# clock.net
KiCad netlist of a schematic drawn in EAGLE
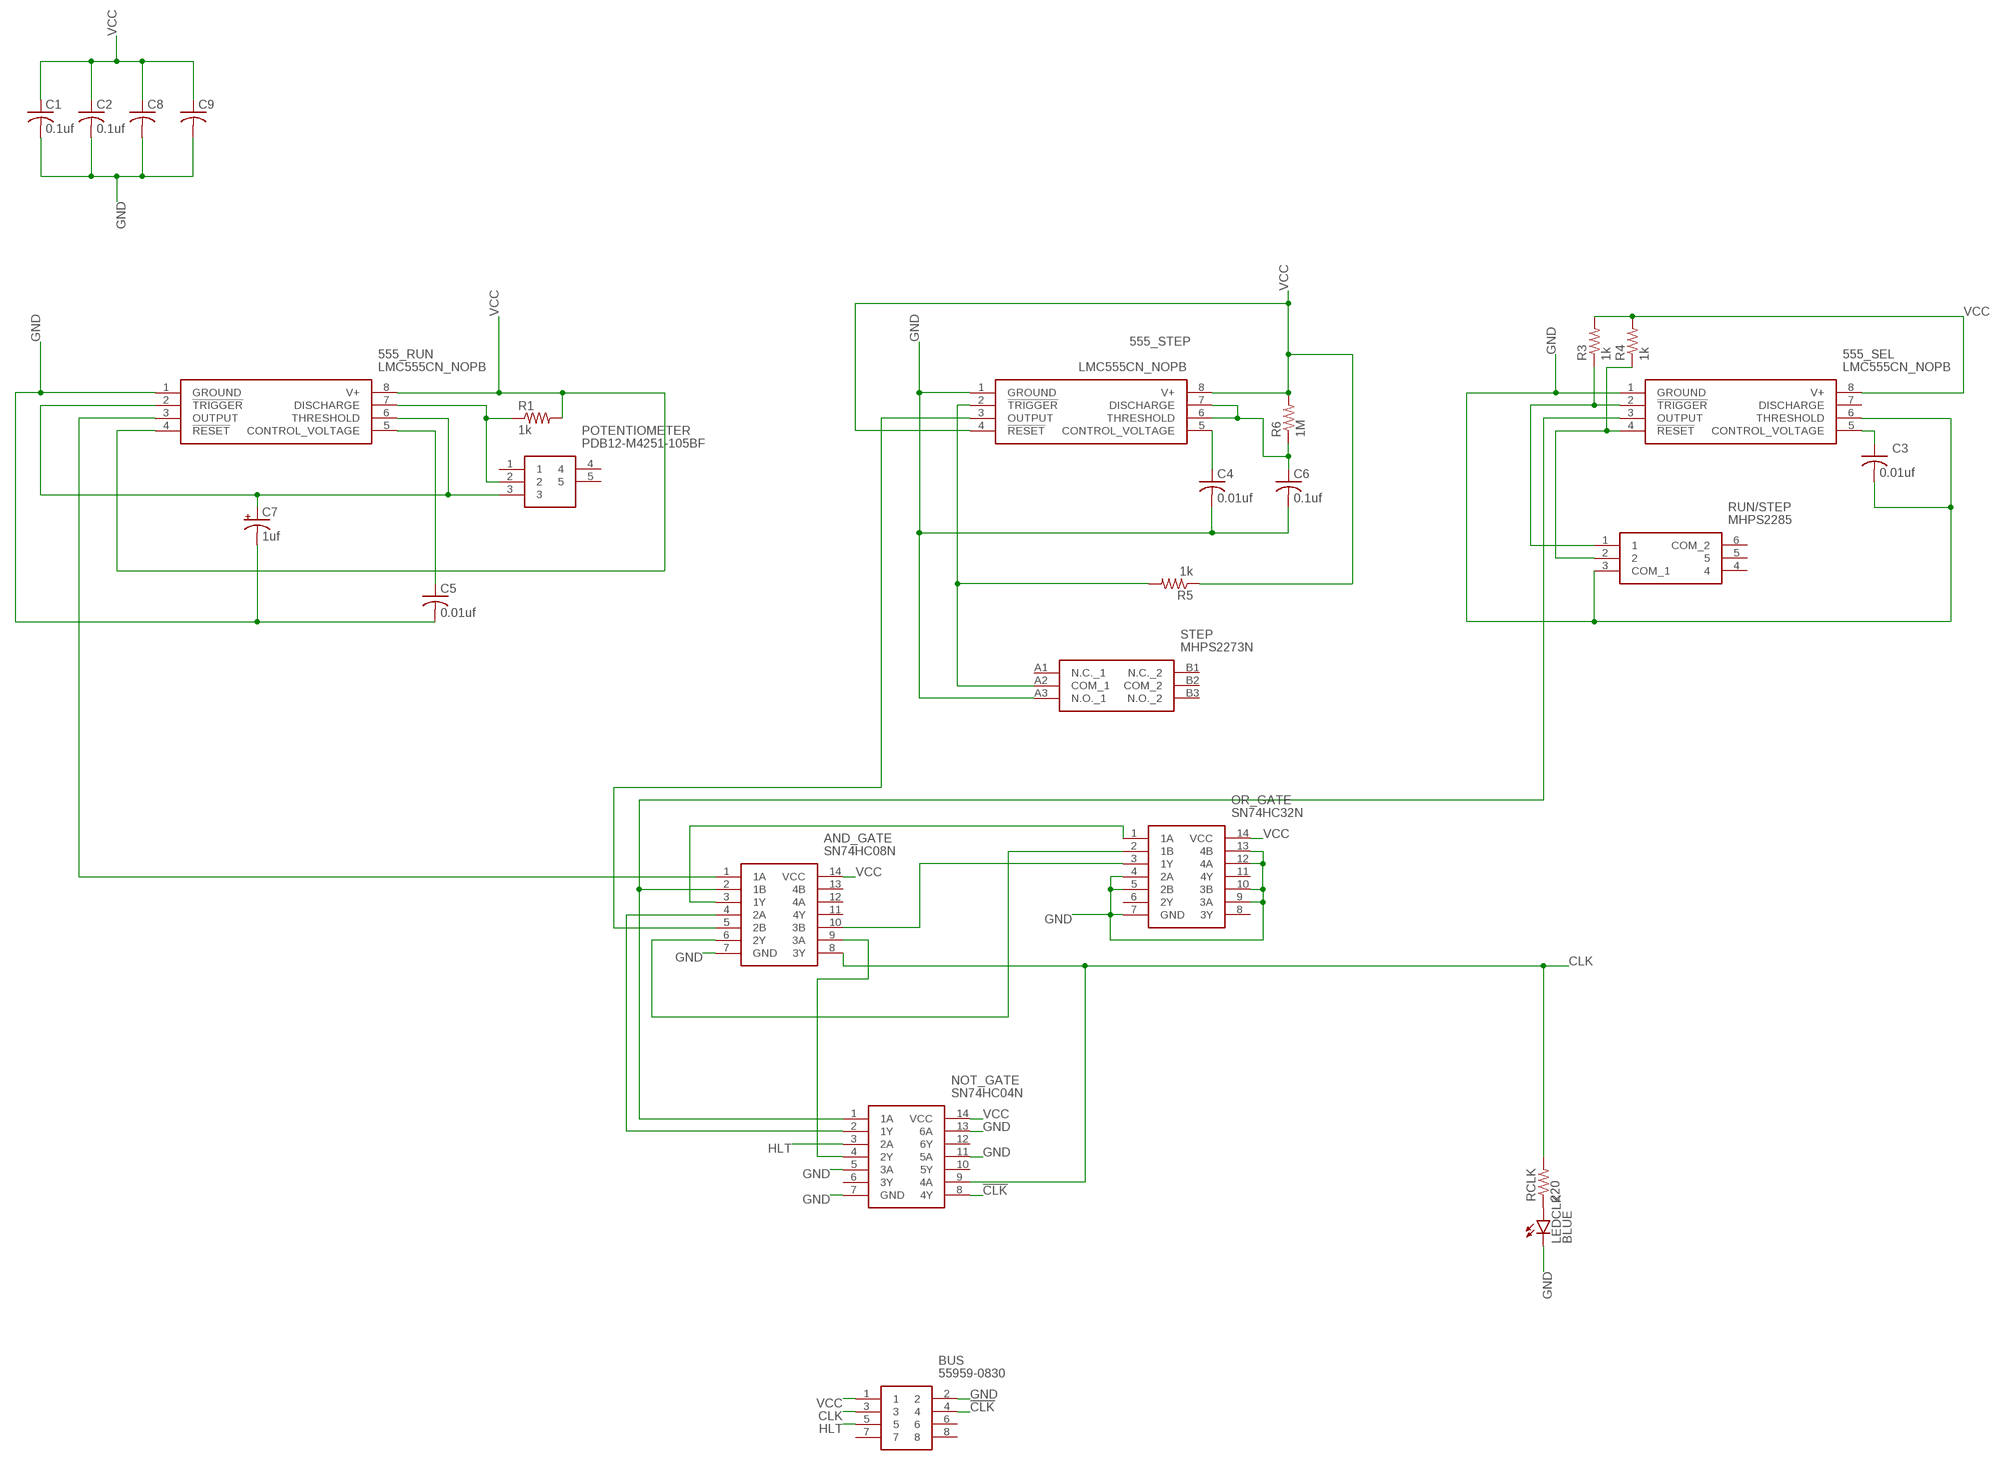
[diagram p0: schematic, sheet 1]

(export (version "E")
  (design (tool "Eeschema 10.0.6"))
  (components
    (comp (ref "555_RUN")
      (value "LMC555CN_NOPB")
      (footprint "eagle-import:DIP794W53P254L959H508Q8N")
      (fields
        (field (name "MANUFACTURER_PART_NUMBER") "LMC555CN/NOPB")
        (field (name "MOUSER_PART_NUMBER") "926-LMC555CN/NOPB")
      )
      (libsource (lib "eagle-import") (part "LMC555CN_NOPB"))
    )
    (comp (ref "555_SEL")
      (value "LMC555CN_NOPB")
      (footprint "eagle-import:DIP794W53P254L959H508Q8N")
      (fields
        (field (name "MANUFACTURER_PART_NUMBER") "LMC555CN/NOPB")
        (field (name "MOUSER_PART_NUMBER") "926-LMC555CN/NOPB")
      )
      (libsource (lib "eagle-import") (part "LMC555CN_NOPB"))
    )
    (comp (ref "555_STEP")
      (value "LMC555CN_NOPB")
      (footprint "eagle-import:DIP794W53P254L959H508Q8N")
      (fields
        (field (name "MANUFACTURER_PART_NUMBER") "LMC555CN/NOPB")
        (field (name "MOUSER_PART_NUMBER") "926-LMC555CN/NOPB")
      )
      (libsource (lib "eagle-import") (part "LMC555CN_NOPB"))
    )
    (comp (ref "AND_GATE")
      (value "SN74HC08N")
      (footprint "eagle-import:DIP794W53P254L1930H508Q14N")
      (fields (field (name "MOUSER_PART_NUMBER") "595-SN74HC08N"))
      (libsource (lib "eagle-import") (part "SN74HC08N"))
    )
    (comp (ref "BUS")
      (value "55959-0830")
      (footprint "eagle-import:SHDR8W65P250X200_2X4_1140X1400")
      (fields (field (name "MOUSER_PART_NUMBER") "538-55959-0830"))
      (libsource (lib "eagle-import") (part "55959-0830"))
    )
    (comp (ref "C1")
      (value "0.1uf")
      (footprint "eagle-import:C025-024X044")
      (libsource (lib "eagle-import") (part "C-US025-024X044"))
    )
    (comp (ref "C2")
      (value "0.1uf")
      (footprint "eagle-import:C025-024X044")
      (libsource (lib "eagle-import") (part "C-US025-024X044"))
    )
    (comp (ref "C3")
      (value "0.01uf")
      (footprint "eagle-import:C025-024X044")
      (libsource (lib "eagle-import") (part "C-US025-024X044"))
    )
    (comp (ref "C4")
      (value "0.01uf")
      (footprint "eagle-import:C025-024X044")
      (libsource (lib "eagle-import") (part "C-US025-024X044"))
    )
    (comp (ref "C5")
      (value "0.01uf")
      (footprint "eagle-import:C025-024X044")
      (libsource (lib "eagle-import") (part "C-US025-024X044"))
    )
    (comp (ref "C6")
      (value "0.1uf")
      (footprint "eagle-import:C025-024X044")
      (libsource (lib "eagle-import") (part "C-US025-024X044"))
    )
    (comp (ref "C7")
      (value "1uf")
      (footprint "eagle-import:E5-5")
      (libsource (lib "eagle-import") (part "CPOL-USE5-5"))
    )
    (comp (ref "C8")
      (value "C-US025-024X044")
      (footprint "eagle-import:C025-024X044")
      (libsource (lib "eagle-import") (part "C-US025-024X044"))
    )
    (comp (ref "C9")
      (value "C-US025-024X044")
      (footprint "eagle-import:C025-024X044")
      (libsource (lib "eagle-import") (part "C-US025-024X044"))
    )
    (comp (ref "LEDCLK")
      (value "BLUE")
      (footprint "eagle-import:LED3MM")
      (libsource (lib "eagle-import") (part "LED3MM"))
    )
    (comp (ref "NOT_GATE")
      (value "SN74HC04N")
      (footprint "eagle-import:DIP794W53P254L1930H508Q14N")
      (fields (field (name "MOUSER_PART_NUMBER") "595-SN74HC04N"))
      (libsource (lib "eagle-import") (part "SN74HC04N"))
    )
    (comp (ref "OR_GATE")
      (value "SN74HC32N")
      (footprint "eagle-import:DIP794W53P254L1930H508Q14N")
      (fields (field (name "MOUSER_PART_NUMBER") "595-SN74HC32N"))
      (libsource (lib "eagle-import") (part "SN74HC32N"))
    )
    (comp (ref "POTENTIOMETER")
      (value "PDB12-M4251-105BF")
      (footprint "eagle-import:PDB12M4251105BF")
      (fields (field (name "MOUSER_PART_NUMBER") "652-PDB12-M4251105BF"))
      (libsource (lib "eagle-import") (part "PDB12-M4251-105BF"))
    )
    (comp (ref "R1")
      (value "1k")
      (footprint "eagle-import:0204_7")
      (libsource (lib "eagle-import") (part "R-US_0204/7"))
    )
    (comp (ref "R3")
      (value "1k")
      (footprint "eagle-import:0204_7")
      (libsource (lib "eagle-import") (part "R-US_0204/7"))
    )
    (comp (ref "R4")
      (value "1k")
      (footprint "eagle-import:0204_7")
      (libsource (lib "eagle-import") (part "R-US_0204/7"))
    )
    (comp (ref "R5")
      (value "1k")
      (footprint "eagle-import:0204_7")
      (libsource (lib "eagle-import") (part "R-US_0204/7"))
    )
    (comp (ref "R6")
      (value "1M")
      (footprint "eagle-import:0204_7")
      (libsource (lib "eagle-import") (part "R-US_0204/7"))
    )
    (comp (ref "RCLK")
      (value "220")
      (footprint "eagle-import:0204_7")
      (libsource (lib "eagle-import") (part "R-US_0204/7"))
    )
    (comp (ref "RUN/STEP")
      (value "MHPS2285")
      (footprint "eagle-import:MHPS2285")
      (fields (field (name "MOUSER_PART_NUMBER") "642-MHPS2285"))
      (libsource (lib "eagle-import") (part "MHPS2285"))
    )
    (comp (ref "STEP")
      (value "MHPS2273N")
      (footprint "eagle-import:MHPS2273N")
      (fields (field (name "MOUSER_PART_NUMBER") "642-MHPS2273N"))
      (libsource (lib "eagle-import") (part "MHPS2273N"))
    )
  )
  (nets
    (net (code "1") (name "/CLK") (class "Default")
      (node (ref "AND_GATE") (pin "8") (pinfunction "3Y_8") (pintype "bidirectional"))
      (node (ref "BUS") (pin "3") (pinfunction "3_3") (pintype "bidirectional"))
      (node (ref "NOT_GATE") (pin "9") (pinfunction "4A_9") (pintype "bidirectional"))
      (node (ref "RCLK") (pin "2") (pinfunction "2_2") (pintype "passive"))
    )
    (net (code "2") (name "/GND") (class "Default")
      (node (ref "555_RUN") (pin "1") (pinfunction "GROUND_1") (pintype "bidirectional"))
      (node (ref "555_SEL") (pin "1") (pinfunction "GROUND_1") (pintype "bidirectional"))
      (node (ref "555_SEL") (pin "6") (pinfunction "THRESHOLD_6") (pintype "bidirectional"))
      (node (ref "555_STEP") (pin "1") (pinfunction "GROUND_1") (pintype "bidirectional"))
      (node (ref "AND_GATE") (pin "7") (pinfunction "GND_7") (pintype "bidirectional"))
      (node (ref "BUS") (pin "2") (pinfunction "2_2") (pintype "bidirectional"))
      (node (ref "C1") (pin "2") (pinfunction "2_2") (pintype "passive"))
      (node (ref "C2") (pin "2") (pinfunction "2_2") (pintype "passive"))
      (node (ref "C3") (pin "2") (pinfunction "2_2") (pintype "passive"))
      (node (ref "C4") (pin "2") (pinfunction "2_2") (pintype "passive"))
      (node (ref "C5") (pin "2") (pinfunction "2_2") (pintype "passive"))
      (node (ref "C6") (pin "2") (pinfunction "2_2") (pintype "passive"))
      (node (ref "C7") (pin "-") (pinfunction "-_-") (pintype "passive"))
      (node (ref "C8") (pin "2") (pinfunction "2_2") (pintype "passive"))
      (node (ref "C9") (pin "2") (pinfunction "2_2") (pintype "passive"))
      (node (ref "LEDCLK") (pin "K") (pinfunction "C_K") (pintype "passive"))
      (node (ref "NOT_GATE") (pin "11") (pinfunction "5A_11") (pintype "bidirectional"))
      (node (ref "NOT_GATE") (pin "13") (pinfunction "6A_13") (pintype "bidirectional"))
      (node (ref "NOT_GATE") (pin "5") (pinfunction "3A_5") (pintype "bidirectional"))
      (node (ref "NOT_GATE") (pin "7") (pinfunction "GND_7") (pintype "bidirectional"))
      (node (ref "OR_GATE") (pin "10") (pinfunction "3B_10") (pintype "bidirectional"))
      (node (ref "OR_GATE") (pin "12") (pinfunction "4A_12") (pintype "bidirectional"))
      (node (ref "OR_GATE") (pin "13") (pinfunction "4B_13") (pintype "bidirectional"))
      (node (ref "OR_GATE") (pin "4") (pinfunction "2A_4") (pintype "bidirectional"))
      (node (ref "OR_GATE") (pin "5") (pinfunction "2B_5") (pintype "bidirectional"))
      (node (ref "OR_GATE") (pin "7") (pinfunction "GND_7") (pintype "bidirectional"))
      (node (ref "OR_GATE") (pin "9") (pinfunction "3A_9") (pintype "bidirectional"))
      (node (ref "RUN/STEP") (pin "3") (pinfunction "COM_1_3") (pintype "bidirectional"))
      (node (ref "STEP") (pin "A3") (pinfunction "N.O._1_A3") (pintype "bidirectional"))
    )
    (net (code "3") (name "/HLT") (class "Default")
      (node (ref "BUS") (pin "5") (pinfunction "5_5") (pintype "bidirectional"))
      (node (ref "NOT_GATE") (pin "3") (pinfunction "2A_3") (pintype "bidirectional"))
    )
    (net (code "4") (name "/VCC") (class "Default")
      (node (ref "555_RUN") (pin "4") (pinfunction "~{RESET}_4") (pintype "bidirectional"))
      (node (ref "555_RUN") (pin "8") (pinfunction "V+_8") (pintype "bidirectional"))
      (node (ref "555_SEL") (pin "8") (pinfunction "V+_8") (pintype "bidirectional"))
      (node (ref "555_STEP") (pin "4") (pinfunction "~{RESET}_4") (pintype "bidirectional"))
      (node (ref "555_STEP") (pin "8") (pinfunction "V+_8") (pintype "bidirectional"))
      (node (ref "AND_GATE") (pin "14") (pinfunction "VCC_14") (pintype "bidirectional"))
      (node (ref "BUS") (pin "1") (pinfunction "1_1") (pintype "bidirectional"))
      (node (ref "C1") (pin "1") (pinfunction "1_1") (pintype "passive"))
      (node (ref "C2") (pin "1") (pinfunction "1_1") (pintype "passive"))
      (node (ref "C8") (pin "1") (pinfunction "1_1") (pintype "passive"))
      (node (ref "C9") (pin "1") (pinfunction "1_1") (pintype "passive"))
      (node (ref "NOT_GATE") (pin "14") (pinfunction "VCC_14") (pintype "bidirectional"))
      (node (ref "OR_GATE") (pin "14") (pinfunction "VCC_14") (pintype "bidirectional"))
      (node (ref "R1") (pin "2") (pinfunction "2_2") (pintype "passive"))
      (node (ref "R3") (pin "2") (pinfunction "2_2") (pintype "passive"))
      (node (ref "R4") (pin "2") (pinfunction "2_2") (pintype "passive"))
      (node (ref "R5") (pin "1") (pinfunction "1_1") (pintype "passive"))
      (node (ref "R6") (pin "2") (pinfunction "2_2") (pintype "passive"))
    )
    (net (code "5") (name "/~{CLK}") (class "Default")
      (node (ref "BUS") (pin "4") (pinfunction "4_4") (pintype "bidirectional"))
      (node (ref "NOT_GATE") (pin "8") (pinfunction "4Y_8") (pintype "bidirectional"))
    )
    (net (code "6") (name "Net-(555_RUN-CONTROL_VOLTAGE)") (class "Default")
      (node (ref "555_RUN") (pin "5") (pinfunction "CONTROL_VOLTAGE_5") (pintype "bidirectional"))
      (node (ref "C5") (pin "1") (pinfunction "1_1") (pintype "passive"))
    )
    (net (code "7") (name "Net-(555_RUN-DISCHARGE)") (class "Default")
      (node (ref "555_RUN") (pin "7") (pinfunction "DISCHARGE_7") (pintype "bidirectional"))
      (node (ref "POTENTIOMETER") (pin "2") (pinfunction "2_2") (pintype "bidirectional"))
      (node (ref "R1") (pin "1") (pinfunction "1_1") (pintype "passive"))
    )
    (net (code "8") (name "Net-(555_RUN-OUTPUT)") (class "Default")
      (node (ref "555_RUN") (pin "3") (pinfunction "OUTPUT_3") (pintype "output"))
      (node (ref "AND_GATE") (pin "1") (pinfunction "1A_1") (pintype "bidirectional"))
    )
    (net (code "9") (name "Net-(555_RUN-THRESHOLD)") (class "Default")
      (node (ref "555_RUN") (pin "2") (pinfunction "~{TRIGGER}_2") (pintype "bidirectional"))
      (node (ref "555_RUN") (pin "6") (pinfunction "THRESHOLD_6") (pintype "bidirectional"))
      (node (ref "C7") (pin "+") (pinfunction "+_+") (pintype "passive"))
      (node (ref "POTENTIOMETER") (pin "3") (pinfunction "3_3") (pintype "bidirectional"))
    )
    (net (code "10") (name "Net-(555_SEL-CONTROL_VOLTAGE)") (class "Default")
      (node (ref "555_SEL") (pin "5") (pinfunction "CONTROL_VOLTAGE_5") (pintype "bidirectional"))
      (node (ref "C3") (pin "1") (pinfunction "1_1") (pintype "passive"))
    )
    (net (code "11") (name "Net-(555_SEL-OUTPUT)") (class "Default")
      (node (ref "555_SEL") (pin "3") (pinfunction "OUTPUT_3") (pintype "output"))
      (node (ref "AND_GATE") (pin "2") (pinfunction "1B_2") (pintype "bidirectional"))
      (node (ref "NOT_GATE") (pin "1") (pinfunction "1A_1") (pintype "bidirectional"))
    )
    (net (code "12") (name "Net-(555_SEL-~{RESET})") (class "Default")
      (node (ref "555_SEL") (pin "4") (pinfunction "~{RESET}_4") (pintype "bidirectional"))
      (node (ref "R4") (pin "1") (pinfunction "1_1") (pintype "passive"))
      (node (ref "RUN/STEP") (pin "2") (pinfunction "2_2") (pintype "bidirectional"))
    )
    (net (code "13") (name "Net-(555_SEL-~{TRIGGER})") (class "Default")
      (node (ref "555_SEL") (pin "2") (pinfunction "~{TRIGGER}_2") (pintype "bidirectional"))
      (node (ref "R3") (pin "1") (pinfunction "1_1") (pintype "passive"))
      (node (ref "RUN/STEP") (pin "1") (pinfunction "1_1") (pintype "bidirectional"))
    )
    (net (code "14") (name "Net-(555_STEP-CONTROL_VOLTAGE)") (class "Default")
      (node (ref "555_STEP") (pin "5") (pinfunction "CONTROL_VOLTAGE_5") (pintype "bidirectional"))
      (node (ref "C4") (pin "1") (pinfunction "1_1") (pintype "passive"))
    )
    (net (code "15") (name "Net-(555_STEP-DISCHARGE)") (class "Default")
      (node (ref "555_STEP") (pin "6") (pinfunction "THRESHOLD_6") (pintype "bidirectional"))
      (node (ref "555_STEP") (pin "7") (pinfunction "DISCHARGE_7") (pintype "bidirectional"))
      (node (ref "C6") (pin "1") (pinfunction "1_1") (pintype "passive"))
      (node (ref "R6") (pin "1") (pinfunction "1_1") (pintype "passive"))
    )
    (net (code "16") (name "Net-(555_STEP-OUTPUT)") (class "Default")
      (node (ref "555_STEP") (pin "3") (pinfunction "OUTPUT_3") (pintype "output"))
      (node (ref "AND_GATE") (pin "5") (pinfunction "2B_5") (pintype "bidirectional"))
    )
    (net (code "17") (name "Net-(555_STEP-~{TRIGGER})") (class "Default")
      (node (ref "555_STEP") (pin "2") (pinfunction "~{TRIGGER}_2") (pintype "bidirectional"))
      (node (ref "R5") (pin "2") (pinfunction "2_2") (pintype "passive"))
      (node (ref "STEP") (pin "A2") (pinfunction "COM_1_A2") (pintype "bidirectional"))
    )
    (net (code "18") (name "Net-(AND_GATE-1Y)") (class "Default")
      (node (ref "AND_GATE") (pin "3") (pinfunction "1Y_3") (pintype "bidirectional"))
      (node (ref "OR_GATE") (pin "1") (pinfunction "1A_1") (pintype "bidirectional"))
    )
    (net (code "19") (name "Net-(AND_GATE-2A)") (class "Default")
      (node (ref "AND_GATE") (pin "4") (pinfunction "2A_4") (pintype "bidirectional"))
      (node (ref "NOT_GATE") (pin "2") (pinfunction "1Y_2") (pintype "bidirectional"))
    )
    (net (code "20") (name "Net-(AND_GATE-2Y)") (class "Default")
      (node (ref "AND_GATE") (pin "6") (pinfunction "2Y_6") (pintype "bidirectional"))
      (node (ref "OR_GATE") (pin "2") (pinfunction "1B_2") (pintype "bidirectional"))
    )
    (net (code "21") (name "Net-(AND_GATE-3A)") (class "Default")
      (node (ref "AND_GATE") (pin "9") (pinfunction "3A_9") (pintype "bidirectional"))
      (node (ref "NOT_GATE") (pin "4") (pinfunction "2Y_4") (pintype "bidirectional"))
    )
    (net (code "22") (name "Net-(AND_GATE-3B)") (class "Default")
      (node (ref "AND_GATE") (pin "10") (pinfunction "3B_10") (pintype "bidirectional"))
      (node (ref "OR_GATE") (pin "3") (pinfunction "1Y_3") (pintype "bidirectional"))
    )
    (net (code "23") (name "Net-(LEDCLK-PadA)") (class "Default")
      (node (ref "LEDCLK") (pin "A") (pinfunction "A_A") (pintype "passive"))
      (node (ref "RCLK") (pin "1") (pinfunction "1_1") (pintype "passive"))
    )
    (net (code "24") (name "unconnected-(555_SEL-DISCHARGE-Pad7)") (class "Default")
      (node (ref "555_SEL") (pin "7") (pinfunction "DISCHARGE_7") (pintype "bidirectional"))
    )
    (net (code "25") (name "unconnected-(AND_GATE-4A-Pad12)") (class "Default")
      (node (ref "AND_GATE") (pin "12") (pinfunction "4A_12") (pintype "bidirectional"))
    )
    (net (code "26") (name "unconnected-(AND_GATE-4B-Pad13)") (class "Default")
      (node (ref "AND_GATE") (pin "13") (pinfunction "4B_13") (pintype "bidirectional"))
    )
    (net (code "27") (name "unconnected-(AND_GATE-4Y-Pad11)") (class "Default")
      (node (ref "AND_GATE") (pin "11") (pinfunction "4Y_11") (pintype "bidirectional"))
    )
    (net (code "28") (name "unconnected-(BUS-Pad6)") (class "Default")
      (node (ref "BUS") (pin "6") (pinfunction "6_6") (pintype "bidirectional"))
    )
    (net (code "29") (name "unconnected-(BUS-Pad7)") (class "Default")
      (node (ref "BUS") (pin "7") (pinfunction "7_7") (pintype "bidirectional"))
    )
    (net (code "30") (name "unconnected-(BUS-Pad8)") (class "Default")
      (node (ref "BUS") (pin "8") (pinfunction "8_8") (pintype "bidirectional"))
    )
    (net (code "31") (name "unconnected-(NOT_GATE-3Y-Pad6)") (class "Default")
      (node (ref "NOT_GATE") (pin "6") (pinfunction "3Y_6") (pintype "bidirectional"))
    )
    (net (code "32") (name "unconnected-(NOT_GATE-5Y-Pad10)") (class "Default")
      (node (ref "NOT_GATE") (pin "10") (pinfunction "5Y_10") (pintype "bidirectional"))
    )
    (net (code "33") (name "unconnected-(NOT_GATE-6Y-Pad12)") (class "Default")
      (node (ref "NOT_GATE") (pin "12") (pinfunction "6Y_12") (pintype "bidirectional"))
    )
    (net (code "34") (name "unconnected-(OR_GATE-2Y-Pad6)") (class "Default")
      (node (ref "OR_GATE") (pin "6") (pinfunction "2Y_6") (pintype "bidirectional"))
    )
    (net (code "35") (name "unconnected-(OR_GATE-3Y-Pad8)") (class "Default")
      (node (ref "OR_GATE") (pin "8") (pinfunction "3Y_8") (pintype "bidirectional"))
    )
    (net (code "36") (name "unconnected-(OR_GATE-4Y-Pad11)") (class "Default")
      (node (ref "OR_GATE") (pin "11") (pinfunction "4Y_11") (pintype "bidirectional"))
    )
    (net (code "37") (name "unconnected-(POTENTIOMETER-Pad1)") (class "Default")
      (node (ref "POTENTIOMETER") (pin "1") (pinfunction "1_1") (pintype "bidirectional"))
    )
    (net (code "38") (name "unconnected-(POTENTIOMETER-Pad4)") (class "Default")
      (node (ref "POTENTIOMETER") (pin "4") (pinfunction "4_4") (pintype "bidirectional"))
    )
    (net (code "39") (name "unconnected-(POTENTIOMETER-Pad5)") (class "Default")
      (node (ref "POTENTIOMETER") (pin "5") (pinfunction "5_5") (pintype "bidirectional"))
    )
    (net (code "40") (name "unconnected-(RUN/STEP-COM_2-Pad6)") (class "Default")
      (node (ref "RUN/STEP") (pin "6") (pinfunction "COM_2_6") (pintype "bidirectional"))
    )
    (net (code "41") (name "unconnected-(RUN/STEP-Pad4)") (class "Default")
      (node (ref "RUN/STEP") (pin "4") (pinfunction "4_4") (pintype "bidirectional"))
    )
    (net (code "42") (name "unconnected-(RUN/STEP-Pad5)") (class "Default")
      (node (ref "RUN/STEP") (pin "5") (pinfunction "5_5") (pintype "bidirectional"))
    )
    (net (code "43") (name "unconnected-(STEP-COM_2-PadB2)") (class "Default")
      (node (ref "STEP") (pin "B2") (pinfunction "COM_2_B2") (pintype "bidirectional"))
    )
    (net (code "44") (name "unconnected-(STEP-N.C._1-PadA1)") (class "Default")
      (node (ref "STEP") (pin "A1") (pinfunction "N.C._1_A1") (pintype "bidirectional"))
    )
    (net (code "45") (name "unconnected-(STEP-N.C._2-PadB1)") (class "Default")
      (node (ref "STEP") (pin "B1") (pinfunction "N.C._2_B1") (pintype "bidirectional"))
    )
    (net (code "46") (name "unconnected-(STEP-N.O._2-PadB3)") (class "Default")
      (node (ref "STEP") (pin "B3") (pinfunction "N.O._2_B3") (pintype "bidirectional"))
    )
  )
)
